# sensor_final_v1.net
KiCad netlist of a schematic drawn in EAGLE
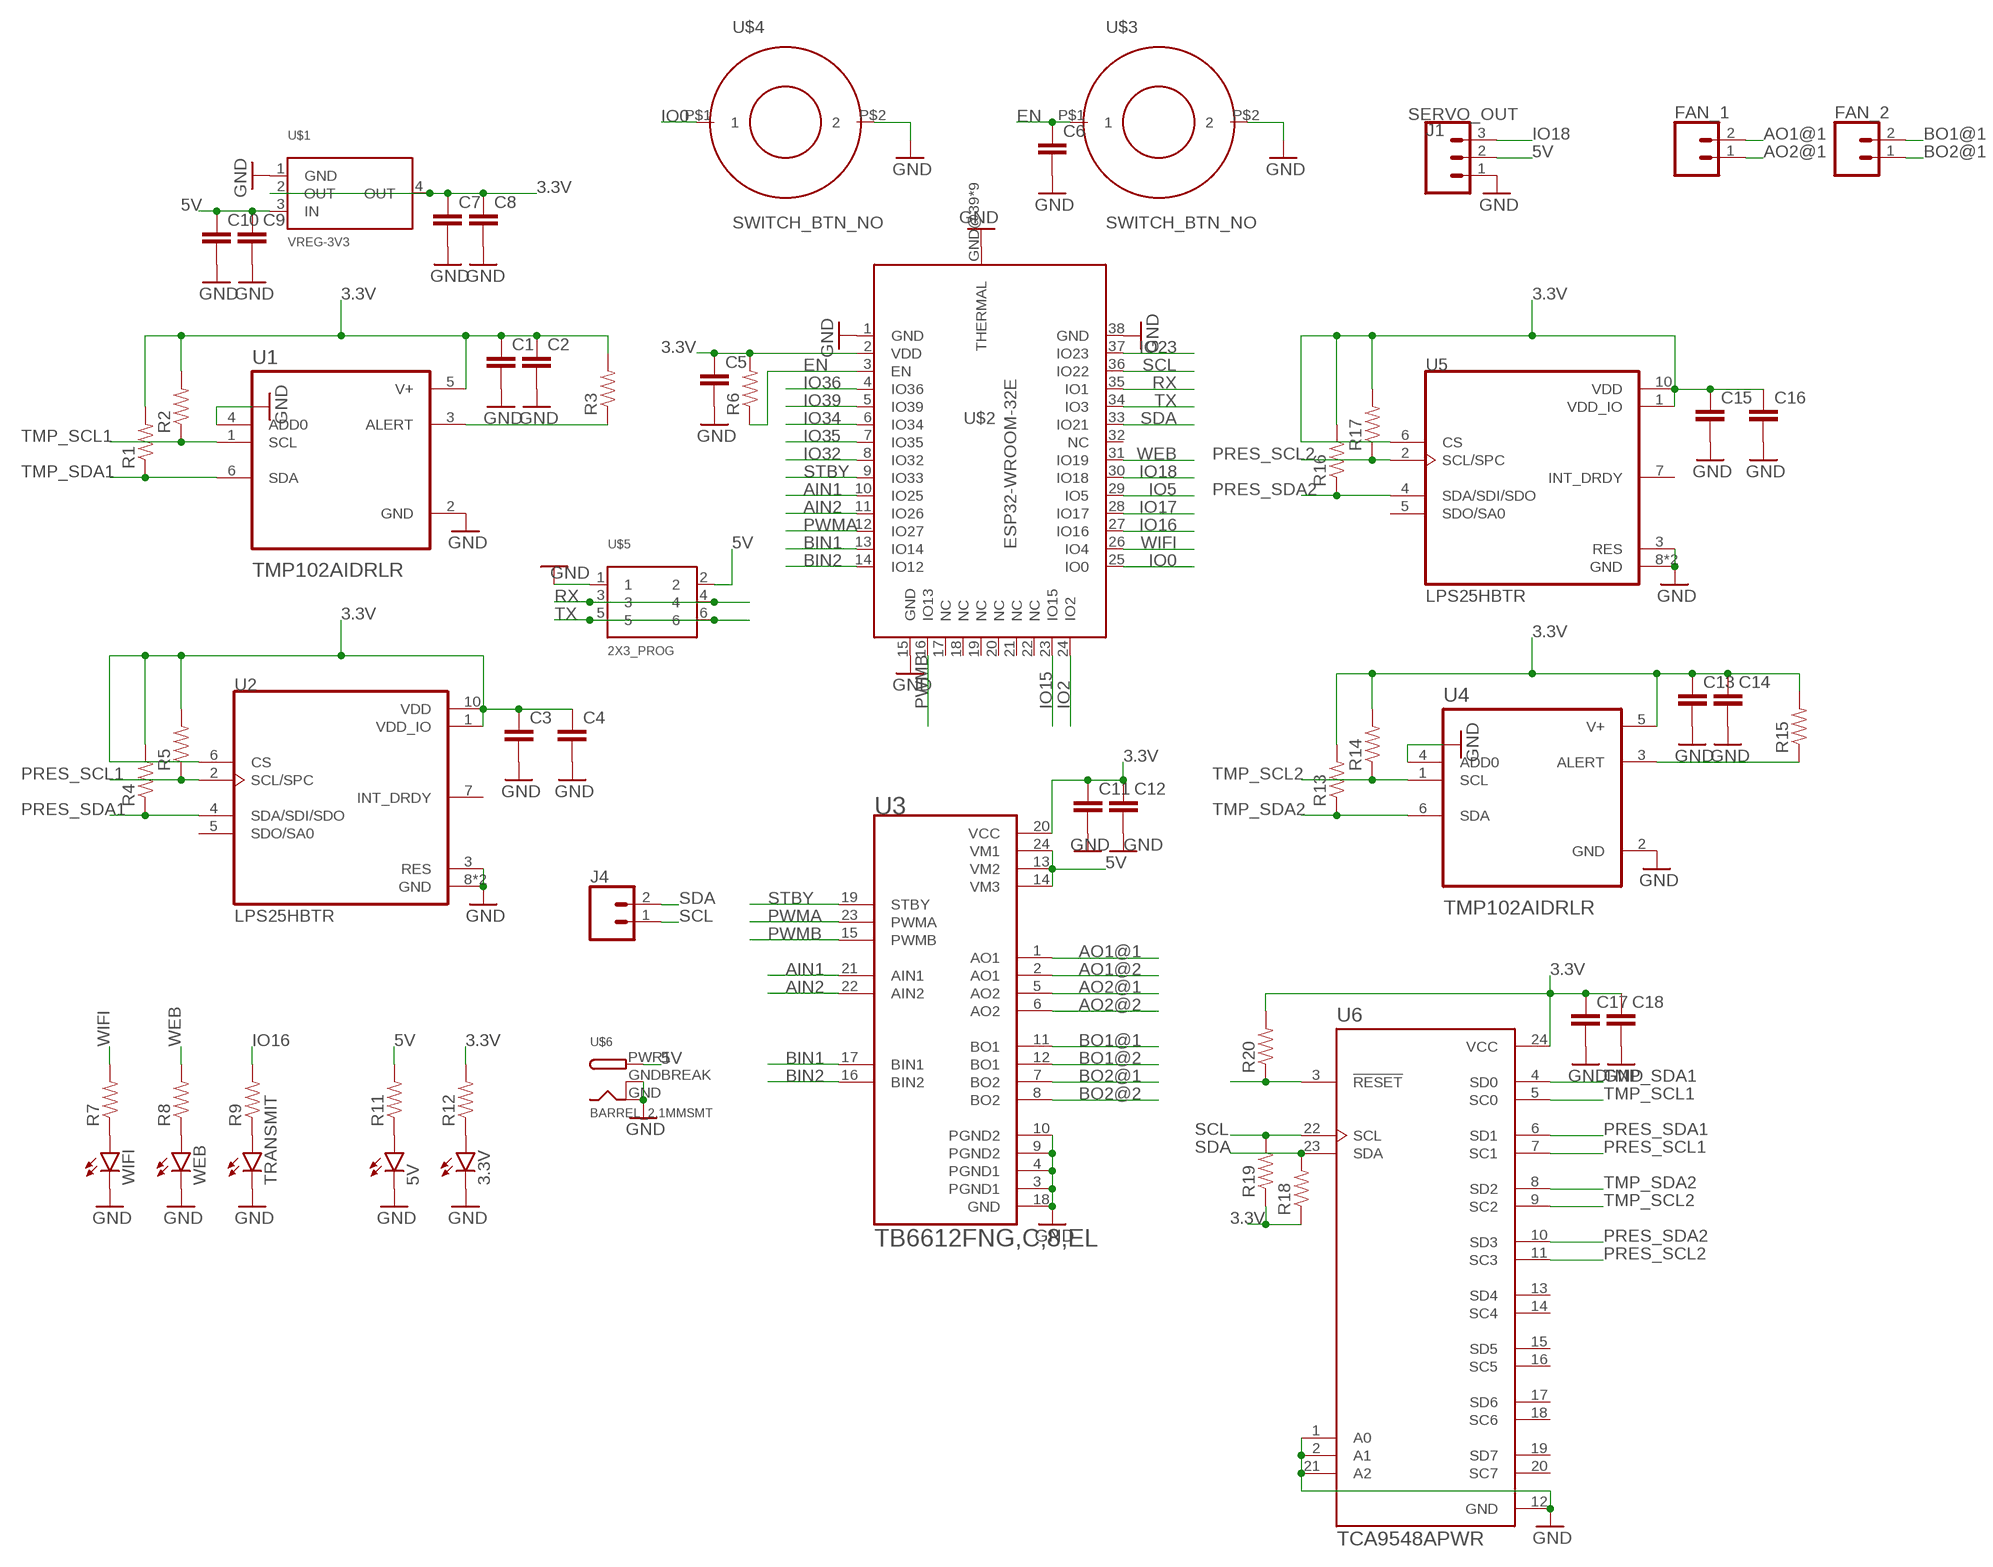
[diagram p0: schematic, sheet 1]

(export (version "E")
  (design (tool "Eeschema 10.0.6"))
  (components
    (comp (ref "3.3V")
      (value "LEDSMT1206")
      (footprint "eagle-import:1206")
      (libsource (lib "eagle-import") (part "LEDSMT1206"))
    )
    (comp (ref "5V")
      (value "LEDSMT1206")
      (footprint "eagle-import:1206")
      (libsource (lib "eagle-import") (part "LEDSMT1206"))
    )
    (comp (ref "C1")
      (value "CAP")
      (footprint "eagle-import:0805")
      (libsource (lib "eagle-import") (part "CAP"))
    )
    (comp (ref "C2")
      (value "CAP")
      (footprint "eagle-import:0805")
      (libsource (lib "eagle-import") (part "CAP"))
    )
    (comp (ref "C3")
      (value "CAP")
      (footprint "eagle-import:0805")
      (libsource (lib "eagle-import") (part "CAP"))
    )
    (comp (ref "C4")
      (value "CAP")
      (footprint "eagle-import:0805")
      (libsource (lib "eagle-import") (part "CAP"))
    )
    (comp (ref "C5")
      (value "CAP")
      (footprint "eagle-import:0805")
      (libsource (lib "eagle-import") (part "CAP"))
    )
    (comp (ref "C6")
      (value "CAP")
      (footprint "eagle-import:0805")
      (libsource (lib "eagle-import") (part "CAP"))
    )
    (comp (ref "C7")
      (value "CAP")
      (footprint "eagle-import:0805")
      (libsource (lib "eagle-import") (part "CAP"))
    )
    (comp (ref "C8")
      (value "CAP")
      (footprint "eagle-import:0805")
      (libsource (lib "eagle-import") (part "CAP"))
    )
    (comp (ref "C9")
      (value "CAP")
      (footprint "eagle-import:0805")
      (libsource (lib "eagle-import") (part "CAP"))
    )
    (comp (ref "C10")
      (value "CAP")
      (footprint "eagle-import:0805")
      (libsource (lib "eagle-import") (part "CAP"))
    )
    (comp (ref "C11")
      (value "CAP")
      (footprint "eagle-import:0805")
      (libsource (lib "eagle-import") (part "CAP"))
    )
    (comp (ref "C12")
      (value "CAP")
      (footprint "eagle-import:0805")
      (libsource (lib "eagle-import") (part "CAP"))
    )
    (comp (ref "C13")
      (value "CAP")
      (footprint "eagle-import:0805")
      (libsource (lib "eagle-import") (part "CAP"))
    )
    (comp (ref "C14")
      (value "CAP")
      (footprint "eagle-import:0805")
      (libsource (lib "eagle-import") (part "CAP"))
    )
    (comp (ref "C15")
      (value "CAP")
      (footprint "eagle-import:0805")
      (libsource (lib "eagle-import") (part "CAP"))
    )
    (comp (ref "C16")
      (value "CAP")
      (footprint "eagle-import:0805")
      (libsource (lib "eagle-import") (part "CAP"))
    )
    (comp (ref "C17")
      (value "CAP")
      (footprint "eagle-import:0805")
      (libsource (lib "eagle-import") (part "CAP"))
    )
    (comp (ref "C18")
      (value "CAP")
      (footprint "eagle-import:0805")
      (libsource (lib "eagle-import") (part "CAP"))
    )
    (comp (ref "FAN_1")
      (value "CONN_02")
      (footprint "eagle-import:1X02")
      (libsource (lib "eagle-import") (part "CONN_02"))
    )
    (comp (ref "FAN_2")
      (value "CONN_02")
      (footprint "eagle-import:1X02")
      (libsource (lib "eagle-import") (part "CONN_02"))
    )
    (comp (ref "J1")
      (value "SERVO_OUT")
      (footprint "eagle-import:1X03")
      (libsource (lib "eagle-import") (part "CONN_03"))
    )
    (comp (ref "J4")
      (value "CONN_02")
      (footprint "eagle-import:1X02")
      (libsource (lib "eagle-import") (part "CONN_02"))
    )
    (comp (ref "R1")
      (value "RES")
      (footprint "eagle-import:0805")
      (libsource (lib "eagle-import") (part "RES"))
    )
    (comp (ref "R2")
      (value "RES")
      (footprint "eagle-import:0805")
      (libsource (lib "eagle-import") (part "RES"))
    )
    (comp (ref "R3")
      (value "RES")
      (footprint "eagle-import:0805")
      (libsource (lib "eagle-import") (part "RES"))
    )
    (comp (ref "R4")
      (value "RES")
      (footprint "eagle-import:0805")
      (libsource (lib "eagle-import") (part "RES"))
    )
    (comp (ref "R5")
      (value "RES")
      (footprint "eagle-import:0805")
      (libsource (lib "eagle-import") (part "RES"))
    )
    (comp (ref "R6")
      (value "RES")
      (footprint "eagle-import:0805")
      (libsource (lib "eagle-import") (part "RES"))
    )
    (comp (ref "R7")
      (value "RES")
      (footprint "eagle-import:0805")
      (libsource (lib "eagle-import") (part "RES"))
    )
    (comp (ref "R8")
      (value "RES")
      (footprint "eagle-import:0805")
      (libsource (lib "eagle-import") (part "RES"))
    )
    (comp (ref "R9")
      (value "RES")
      (footprint "eagle-import:0805")
      (libsource (lib "eagle-import") (part "RES"))
    )
    (comp (ref "R11")
      (value "RES")
      (footprint "eagle-import:0805")
      (libsource (lib "eagle-import") (part "RES"))
    )
    (comp (ref "R12")
      (value "RES")
      (footprint "eagle-import:0805")
      (libsource (lib "eagle-import") (part "RES"))
    )
    (comp (ref "R13")
      (value "RES")
      (footprint "eagle-import:0805")
      (libsource (lib "eagle-import") (part "RES"))
    )
    (comp (ref "R14")
      (value "RES")
      (footprint "eagle-import:0805")
      (libsource (lib "eagle-import") (part "RES"))
    )
    (comp (ref "R15")
      (value "RES")
      (footprint "eagle-import:0805")
      (libsource (lib "eagle-import") (part "RES"))
    )
    (comp (ref "R16")
      (value "RES")
      (footprint "eagle-import:0805")
      (libsource (lib "eagle-import") (part "RES"))
    )
    (comp (ref "R17")
      (value "RES")
      (footprint "eagle-import:0805")
      (libsource (lib "eagle-import") (part "RES"))
    )
    (comp (ref "R18")
      (value "RES")
      (footprint "eagle-import:0805")
      (libsource (lib "eagle-import") (part "RES"))
    )
    (comp (ref "R19")
      (value "RES")
      (footprint "eagle-import:0805")
      (libsource (lib "eagle-import") (part "RES"))
    )
    (comp (ref "R20")
      (value "RES")
      (footprint "eagle-import:0805")
      (libsource (lib "eagle-import") (part "RES"))
    )
    (comp (ref "TRANSMIT")
      (value "LEDSMT1206")
      (footprint "eagle-import:1206")
      (libsource (lib "eagle-import") (part "LEDSMT1206"))
    )
    (comp (ref "U$1")
      (value "VREG-3V3")
      (footprint "eagle-import:R-PDSO-G4_TI")
      (libsource (lib "eagle-import") (part "VREG-3V3"))
    )
    (comp (ref "U$2")
      (value "ESP32-WROOM-32E")
      (footprint "eagle-import:ESP32-WROOM-32E")
      (libsource (lib "eagle-import") (part "ESP32-WROOM-32E"))
    )
    (comp (ref "U$3")
      (value "SWITCH_BTN_NO")
      (footprint "eagle-import:BTN_2")
      (libsource (lib "eagle-import") (part "SWITCH_BTN_NO"))
    )
    (comp (ref "U$4")
      (value "SWITCH_BTN_NO")
      (footprint "eagle-import:BTN_2")
      (libsource (lib "eagle-import") (part "SWITCH_BTN_NO"))
    )
    (comp (ref "U$5")
      (value "2X3_PROG")
      (footprint "eagle-import:2X3_0.1IN")
      (libsource (lib "eagle-import") (part "2X3_PROG"))
    )
    (comp (ref "U$6")
      (value "BARREL_2.1MMSMT")
      (footprint "eagle-import:DCJACK_2MM_SMT")
      (libsource (lib "eagle-import") (part "BARREL_2.1MMSMT"))
    )
    (comp (ref "U1")
      (value "TMP102AIDRLR")
      (footprint "eagle-import:SOT50P160X60-6N")
      (fields (field (name "MF") "Texas Instruments"))
      (libsource (lib "eagle-import") (part "TMP102AIDRLR"))
    )
    (comp (ref "U2")
      (value "LPS25HBTR")
      (footprint "eagle-import:PQFN60P250X250X80-10N")
      (fields (field (name "MF") "STMicroelectronics"))
      (libsource (lib "eagle-import") (part "LPS25HBTR"))
    )
    (comp (ref "U3")
      (value "TB6612FNG,C,8,EL")
      (footprint "eagle-import:SOP65P760X160-24N")
      (fields (field (name "MF") "Toshiba"))
      (libsource (lib "eagle-import") (part "TB6612FNG,C,8,EL"))
    )
    (comp (ref "U4")
      (value "TMP102AIDRLR")
      (footprint "eagle-import:SOT50P160X60-6N")
      (fields (field (name "MF") "Texas Instruments"))
      (libsource (lib "eagle-import") (part "TMP102AIDRLR"))
    )
    (comp (ref "U5")
      (value "LPS25HBTR")
      (footprint "eagle-import:PQFN60P250X250X80-10N")
      (fields (field (name "MF") "STMicroelectronics"))
      (libsource (lib "eagle-import") (part "LPS25HBTR"))
    )
    (comp (ref "U6")
      (value "TCA9548APWR")
      (footprint "eagle-import:SOP65P640X120-24N")
      (fields (field (name "MF") "Texas Instruments"))
      (libsource (lib "eagle-import") (part "TCA9548APWR"))
    )
    (comp (ref "WEB")
      (value "LEDSMT1206")
      (footprint "eagle-import:1206")
      (libsource (lib "eagle-import") (part "LEDSMT1206"))
    )
    (comp (ref "WIFI")
      (value "LEDSMT1206")
      (footprint "eagle-import:1206")
      (libsource (lib "eagle-import") (part "LEDSMT1206"))
    )
  )
  (nets
    (net (code "1") (name "/3.3V") (class "Default")
      (node (ref "C1") (pin "1") (pinfunction "1_1") (pintype "passive"))
      (node (ref "C11") (pin "1") (pinfunction "1_1") (pintype "passive"))
      (node (ref "C12") (pin "1") (pinfunction "1_1") (pintype "passive"))
      (node (ref "C13") (pin "1") (pinfunction "1_1") (pintype "passive"))
      (node (ref "C14") (pin "1") (pinfunction "1_1") (pintype "passive"))
      (node (ref "C15") (pin "1") (pinfunction "1_1") (pintype "passive"))
      (node (ref "C16") (pin "1") (pinfunction "1_1") (pintype "passive"))
      (node (ref "C17") (pin "1") (pinfunction "1_1") (pintype "passive"))
      (node (ref "C18") (pin "1") (pinfunction "1_1") (pintype "passive"))
      (node (ref "C2") (pin "1") (pinfunction "1_1") (pintype "passive"))
      (node (ref "C3") (pin "1") (pinfunction "1_1") (pintype "passive"))
      (node (ref "C4") (pin "1") (pinfunction "1_1") (pintype "passive"))
      (node (ref "C5") (pin "1") (pinfunction "1_1") (pintype "passive"))
      (node (ref "C7") (pin "1") (pinfunction "1_1") (pintype "passive"))
      (node (ref "C8") (pin "1") (pinfunction "1_1") (pintype "passive"))
      (node (ref "R1") (pin "2") (pinfunction "2_2") (pintype "passive"))
      (node (ref "R12") (pin "2") (pinfunction "2_2") (pintype "passive"))
      (node (ref "R13") (pin "2") (pinfunction "2_2") (pintype "passive"))
      (node (ref "R14") (pin "2") (pinfunction "2_2") (pintype "passive"))
      (node (ref "R15") (pin "2") (pinfunction "2_2") (pintype "passive"))
      (node (ref "R16") (pin "2") (pinfunction "2_2") (pintype "passive"))
      (node (ref "R17") (pin "2") (pinfunction "2_2") (pintype "passive"))
      (node (ref "R18") (pin "1") (pinfunction "1_1") (pintype "passive"))
      (node (ref "R19") (pin "1") (pinfunction "1_1") (pintype "passive"))
      (node (ref "R2") (pin "2") (pinfunction "2_2") (pintype "passive"))
      (node (ref "R20") (pin "2") (pinfunction "2_2") (pintype "passive"))
      (node (ref "R3") (pin "2") (pinfunction "2_2") (pintype "passive"))
      (node (ref "R4") (pin "2") (pinfunction "2_2") (pintype "passive"))
      (node (ref "R5") (pin "2") (pinfunction "2_2") (pintype "passive"))
      (node (ref "R6") (pin "2") (pinfunction "2_2") (pintype "passive"))
      (node (ref "U$1") (pin "2") (pinfunction "OUT_2") (pintype "bidirectional"))
      (node (ref "U$1") (pin "4") (pinfunction "OUT_4") (pintype "bidirectional"))
      (node (ref "U$2") (pin "2") (pinfunction "VDD_2") (pintype "bidirectional"))
      (node (ref "U1") (pin "5") (pinfunction "V+_5") (pintype "power_in"))
      (node (ref "U2") (pin "1") (pinfunction "VDD_IO_1") (pintype "power_in"))
      (node (ref "U2") (pin "10") (pinfunction "VDD_10") (pintype "power_in"))
      (node (ref "U2") (pin "6") (pinfunction "CS_6") (pintype "input"))
      (node (ref "U3") (pin "20") (pinfunction "VCC_20") (pintype "power_in"))
      (node (ref "U4") (pin "5") (pinfunction "V+_5") (pintype "power_in"))
      (node (ref "U5") (pin "1") (pinfunction "VDD_IO_1") (pintype "power_in"))
      (node (ref "U5") (pin "10") (pinfunction "VDD_10") (pintype "power_in"))
      (node (ref "U5") (pin "6") (pinfunction "CS_6") (pintype "input"))
      (node (ref "U6") (pin "24") (pinfunction "VCC_24") (pintype "power_in"))
    )
    (net (code "2") (name "/5V") (class "Default")
      (node (ref "C10") (pin "1") (pinfunction "1_1") (pintype "passive"))
      (node (ref "C9") (pin "1") (pinfunction "1_1") (pintype "passive"))
      (node (ref "J1") (pin "2") (pinfunction "2_2") (pintype "passive"))
      (node (ref "R11") (pin "2") (pinfunction "2_2") (pintype "passive"))
      (node (ref "U$1") (pin "3") (pinfunction "IN_3") (pintype "bidirectional"))
      (node (ref "U$5") (pin "2") (pinfunction "2_2") (pintype "bidirectional"))
      (node (ref "U$6") (pin "PWR1") (pinfunction "PWR_PWR1") (pintype "power_in"))
      (node (ref "U3") (pin "13") (pinfunction "VM2_13") (pintype "power_in"))
      (node (ref "U3") (pin "14") (pinfunction "VM3_14") (pintype "power_in"))
      (node (ref "U3") (pin "24") (pinfunction "VM1_24") (pintype "power_in"))
    )
    (net (code "3") (name "/AIN1") (class "Default")
      (node (ref "U$2") (pin "10") (pinfunction "IO25_10") (pintype "bidirectional"))
      (node (ref "U3") (pin "21") (pinfunction "AIN1_21") (pintype "input"))
    )
    (net (code "4") (name "/AIN2") (class "Default")
      (node (ref "U$2") (pin "11") (pinfunction "IO26_11") (pintype "bidirectional"))
      (node (ref "U3") (pin "22") (pinfunction "AIN2_22") (pintype "input"))
    )
    (net (code "5") (name "/AO1@1") (class "Default")
      (node (ref "FAN_1") (pin "2") (pinfunction "2_2") (pintype "passive"))
      (node (ref "U3") (pin "1") (pinfunction "AO1_1") (pintype "output"))
    )
    (net (code "6") (name "/AO1@2") (class "Default")
      (node (ref "U3") (pin "2") (pinfunction "AO1_2") (pintype "output"))
    )
    (net (code "7") (name "/AO2@1") (class "Default")
      (node (ref "FAN_1") (pin "1") (pinfunction "1_1") (pintype "passive"))
      (node (ref "U3") (pin "5") (pinfunction "AO2_5") (pintype "output"))
    )
    (net (code "8") (name "/AO2@2") (class "Default")
      (node (ref "U3") (pin "6") (pinfunction "AO2_6") (pintype "output"))
    )
    (net (code "9") (name "/BIN1") (class "Default")
      (node (ref "U$2") (pin "13") (pinfunction "IO14_13") (pintype "bidirectional"))
      (node (ref "U3") (pin "17") (pinfunction "BIN1_17") (pintype "input"))
    )
    (net (code "10") (name "/BIN2") (class "Default")
      (node (ref "U$2") (pin "14") (pinfunction "IO12_14") (pintype "bidirectional"))
      (node (ref "U3") (pin "16") (pinfunction "BIN2_16") (pintype "input"))
    )
    (net (code "11") (name "/BO1@1") (class "Default")
      (node (ref "FAN_2") (pin "2") (pinfunction "2_2") (pintype "passive"))
      (node (ref "U3") (pin "11") (pinfunction "BO1_11") (pintype "output"))
    )
    (net (code "12") (name "/BO1@2") (class "Default")
      (node (ref "U3") (pin "12") (pinfunction "BO1_12") (pintype "output"))
    )
    (net (code "13") (name "/BO2@1") (class "Default")
      (node (ref "FAN_2") (pin "1") (pinfunction "1_1") (pintype "passive"))
      (node (ref "U3") (pin "7") (pinfunction "BO2_7") (pintype "output"))
    )
    (net (code "14") (name "/BO2@2") (class "Default")
      (node (ref "U3") (pin "8") (pinfunction "BO2_8") (pintype "output"))
    )
    (net (code "15") (name "/EN") (class "Default")
      (node (ref "C6") (pin "1") (pinfunction "1_1") (pintype "passive"))
      (node (ref "R6") (pin "1") (pinfunction "1_1") (pintype "passive"))
      (node (ref "U$2") (pin "3") (pinfunction "EN_3") (pintype "bidirectional"))
      (node (ref "U$3") (pin "P$1") (pinfunction "1_P$1") (pintype "bidirectional"))
    )
    (net (code "16") (name "/IO0") (class "Default")
      (node (ref "U$2") (pin "25") (pinfunction "IO0_25") (pintype "bidirectional"))
      (node (ref "U$4") (pin "P$1") (pinfunction "1_P$1") (pintype "bidirectional"))
    )
    (net (code "17") (name "/IO2") (class "Default")
      (node (ref "U$2") (pin "24") (pinfunction "IO2_24") (pintype "bidirectional"))
    )
    (net (code "18") (name "/IO5") (class "Default")
      (node (ref "U$2") (pin "29") (pinfunction "IO5_29") (pintype "bidirectional"))
    )
    (net (code "19") (name "/IO15") (class "Default")
      (node (ref "U$2") (pin "23") (pinfunction "IO15_23") (pintype "bidirectional"))
    )
    (net (code "20") (name "/IO16") (class "Default")
      (node (ref "R9") (pin "2") (pinfunction "2_2") (pintype "passive"))
      (node (ref "U$2") (pin "27") (pinfunction "IO16_27") (pintype "bidirectional"))
    )
    (net (code "21") (name "/IO17") (class "Default")
      (node (ref "U$2") (pin "28") (pinfunction "IO17_28") (pintype "bidirectional"))
    )
    (net (code "22") (name "/IO18") (class "Default")
      (node (ref "J1") (pin "3") (pinfunction "3_3") (pintype "passive"))
      (node (ref "U$2") (pin "30") (pinfunction "IO18_30") (pintype "bidirectional"))
    )
    (net (code "23") (name "/IO23") (class "Default")
      (node (ref "U$2") (pin "37") (pinfunction "IO23_37") (pintype "bidirectional"))
    )
    (net (code "24") (name "/IO32") (class "Default")
      (node (ref "U$2") (pin "8") (pinfunction "IO32_8") (pintype "bidirectional"))
    )
    (net (code "25") (name "/IO34") (class "Default")
      (node (ref "U$2") (pin "6") (pinfunction "IO34_6") (pintype "bidirectional"))
    )
    (net (code "26") (name "/IO35") (class "Default")
      (node (ref "U$2") (pin "7") (pinfunction "IO35_7") (pintype "bidirectional"))
    )
    (net (code "27") (name "/IO36") (class "Default")
      (node (ref "U$2") (pin "4") (pinfunction "IO36_4") (pintype "bidirectional"))
    )
    (net (code "28") (name "/IO39") (class "Default")
      (node (ref "U$2") (pin "5") (pinfunction "IO39_5") (pintype "bidirectional"))
    )
    (net (code "29") (name "/PRES_SCL1") (class "Default")
      (node (ref "R5") (pin "1") (pinfunction "1_1") (pintype "passive"))
      (node (ref "U2") (pin "2") (pinfunction "SCL/SPC_2") (pintype "input"))
      (node (ref "U6") (pin "7") (pinfunction "SC1_7") (pintype "bidirectional"))
    )
    (net (code "30") (name "/PRES_SCL2") (class "Default")
      (node (ref "R17") (pin "1") (pinfunction "1_1") (pintype "passive"))
      (node (ref "U5") (pin "2") (pinfunction "SCL/SPC_2") (pintype "input"))
      (node (ref "U6") (pin "11") (pinfunction "SC3_11") (pintype "bidirectional"))
    )
    (net (code "31") (name "/PRES_SDA1") (class "Default")
      (node (ref "R4") (pin "1") (pinfunction "1_1") (pintype "passive"))
      (node (ref "U2") (pin "4") (pinfunction "SDA/SDI/SDO_4") (pintype "bidirectional"))
      (node (ref "U6") (pin "6") (pinfunction "SD1_6") (pintype "bidirectional"))
    )
    (net (code "32") (name "/PRES_SDA2") (class "Default")
      (node (ref "R16") (pin "1") (pinfunction "1_1") (pintype "passive"))
      (node (ref "U5") (pin "4") (pinfunction "SDA/SDI/SDO_4") (pintype "bidirectional"))
      (node (ref "U6") (pin "10") (pinfunction "SD3_10") (pintype "bidirectional"))
    )
    (net (code "33") (name "/PWMA") (class "Default")
      (node (ref "U$2") (pin "12") (pinfunction "IO27_12") (pintype "bidirectional"))
      (node (ref "U3") (pin "23") (pinfunction "PWMA_23") (pintype "input"))
    )
    (net (code "34") (name "/PWMB") (class "Default")
      (node (ref "U$2") (pin "16") (pinfunction "IO13_16") (pintype "bidirectional"))
      (node (ref "U3") (pin "15") (pinfunction "PWMB_15") (pintype "input"))
    )
    (net (code "35") (name "/RX") (class "Default")
      (node (ref "U$2") (pin "35") (pinfunction "IO1_35") (pintype "bidirectional"))
      (node (ref "U$5") (pin "3") (pinfunction "3_3") (pintype "bidirectional"))
      (node (ref "U$5") (pin "4") (pinfunction "4_4") (pintype "bidirectional"))
    )
    (net (code "36") (name "/SCL") (class "Default")
      (node (ref "J4") (pin "1") (pinfunction "1_1") (pintype "passive"))
      (node (ref "R19") (pin "2") (pinfunction "2_2") (pintype "passive"))
      (node (ref "U$2") (pin "36") (pinfunction "IO22_36") (pintype "bidirectional"))
      (node (ref "U6") (pin "22") (pinfunction "SCL_22") (pintype "input"))
    )
    (net (code "37") (name "/SDA") (class "Default")
      (node (ref "J4") (pin "2") (pinfunction "2_2") (pintype "passive"))
      (node (ref "R18") (pin "2") (pinfunction "2_2") (pintype "passive"))
      (node (ref "U$2") (pin "33") (pinfunction "IO21_33") (pintype "bidirectional"))
      (node (ref "U6") (pin "23") (pinfunction "SDA_23") (pintype "bidirectional"))
    )
    (net (code "38") (name "/STBY") (class "Default")
      (node (ref "U$2") (pin "9") (pinfunction "IO33_9") (pintype "bidirectional"))
      (node (ref "U3") (pin "19") (pinfunction "STBY_19") (pintype "input"))
    )
    (net (code "39") (name "/TMP_SCL1") (class "Default")
      (node (ref "R2") (pin "1") (pinfunction "1_1") (pintype "passive"))
      (node (ref "U1") (pin "1") (pinfunction "SCL_1") (pintype "input"))
      (node (ref "U6") (pin "5") (pinfunction "SC0_5") (pintype "bidirectional"))
    )
    (net (code "40") (name "/TMP_SCL2") (class "Default")
      (node (ref "R14") (pin "1") (pinfunction "1_1") (pintype "passive"))
      (node (ref "U4") (pin "1") (pinfunction "SCL_1") (pintype "input"))
      (node (ref "U6") (pin "9") (pinfunction "SC2_9") (pintype "bidirectional"))
    )
    (net (code "41") (name "/TMP_SDA1") (class "Default")
      (node (ref "R1") (pin "1") (pinfunction "1_1") (pintype "passive"))
      (node (ref "U1") (pin "6") (pinfunction "SDA_6") (pintype "bidirectional"))
      (node (ref "U6") (pin "4") (pinfunction "SD0_4") (pintype "bidirectional"))
    )
    (net (code "42") (name "/TMP_SDA2") (class "Default")
      (node (ref "R13") (pin "1") (pinfunction "1_1") (pintype "passive"))
      (node (ref "U4") (pin "6") (pinfunction "SDA_6") (pintype "bidirectional"))
      (node (ref "U6") (pin "8") (pinfunction "SD2_8") (pintype "bidirectional"))
    )
    (net (code "43") (name "/TX") (class "Default")
      (node (ref "U$2") (pin "34") (pinfunction "IO3_34") (pintype "bidirectional"))
      (node (ref "U$5") (pin "5") (pinfunction "5_5") (pintype "bidirectional"))
      (node (ref "U$5") (pin "6") (pinfunction "6_6") (pintype "bidirectional"))
    )
    (net (code "44") (name "/WEB") (class "Default")
      (node (ref "R8") (pin "2") (pinfunction "2_2") (pintype "passive"))
      (node (ref "U$2") (pin "31") (pinfunction "IO19_31") (pintype "bidirectional"))
    )
    (net (code "45") (name "/WIFI") (class "Default")
      (node (ref "R7") (pin "2") (pinfunction "2_2") (pintype "passive"))
      (node (ref "U$2") (pin "26") (pinfunction "IO4_26") (pintype "bidirectional"))
    )
    (net (code "46") (name "GND") (class "Default")
      (node (ref "3.3V") (pin "C") (pinfunction "C_C") (pintype "passive"))
      (node (ref "5V") (pin "C") (pinfunction "C_C") (pintype "passive"))
      (node (ref "C1") (pin "2") (pinfunction "2_2") (pintype "passive"))
      (node (ref "C10") (pin "2") (pinfunction "2_2") (pintype "passive"))
      (node (ref "C11") (pin "2") (pinfunction "2_2") (pintype "passive"))
      (node (ref "C12") (pin "2") (pinfunction "2_2") (pintype "passive"))
      (node (ref "C13") (pin "2") (pinfunction "2_2") (pintype "passive"))
      (node (ref "C14") (pin "2") (pinfunction "2_2") (pintype "passive"))
      (node (ref "C15") (pin "2") (pinfunction "2_2") (pintype "passive"))
      (node (ref "C16") (pin "2") (pinfunction "2_2") (pintype "passive"))
      (node (ref "C17") (pin "2") (pinfunction "2_2") (pintype "passive"))
      (node (ref "C18") (pin "2") (pinfunction "2_2") (pintype "passive"))
      (node (ref "C2") (pin "2") (pinfunction "2_2") (pintype "passive"))
      (node (ref "C3") (pin "2") (pinfunction "2_2") (pintype "passive"))
      (node (ref "C4") (pin "2") (pinfunction "2_2") (pintype "passive"))
      (node (ref "C5") (pin "2") (pinfunction "2_2") (pintype "passive"))
      (node (ref "C6") (pin "2") (pinfunction "2_2") (pintype "passive"))
      (node (ref "C7") (pin "2") (pinfunction "2_2") (pintype "passive"))
      (node (ref "C8") (pin "2") (pinfunction "2_2") (pintype "passive"))
      (node (ref "C9") (pin "2") (pinfunction "2_2") (pintype "passive"))
      (node (ref "J1") (pin "1") (pinfunction "1_1") (pintype "passive"))
      (node (ref "TRANSMIT") (pin "C") (pinfunction "C_C") (pintype "passive"))
      (node (ref "U$1") (pin "1") (pinfunction "GND_1") (pintype "bidirectional"))
      (node (ref "U$2") (pin "1") (pinfunction "GND_1") (pintype "bidirectional"))
      (node (ref "U$2") (pin "15") (pinfunction "GND_15") (pintype "bidirectional"))
      (node (ref "U$2") (pin "38") (pinfunction "GND_38") (pintype "bidirectional"))
      (node (ref "U$2") (pin "GND@39") (pinfunction "THERMAL_GND@39") (pintype "bidirectional"))
      (node (ref "U$2") (pin "GND@40") (pinfunction "THERMAL_GND@40") (pintype "bidirectional"))
      (node (ref "U$2") (pin "GND@41") (pinfunction "THERMAL_GND@41") (pintype "bidirectional"))
      (node (ref "U$2") (pin "GND@42") (pinfunction "THERMAL_GND@42") (pintype "bidirectional"))
      (node (ref "U$2") (pin "GND@43") (pinfunction "THERMAL_GND@43") (pintype "bidirectional"))
      (node (ref "U$2") (pin "GND@44") (pinfunction "THERMAL_GND@44") (pintype "bidirectional"))
      (node (ref "U$2") (pin "GND@45") (pinfunction "THERMAL_GND@45") (pintype "bidirectional"))
      (node (ref "U$2") (pin "GND@46") (pinfunction "THERMAL_GND@46") (pintype "bidirectional"))
      (node (ref "U$2") (pin "GND@47") (pinfunction "THERMAL_GND@47") (pintype "bidirectional"))
      (node (ref "U$3") (pin "P$2") (pinfunction "2_P$2") (pintype "bidirectional"))
      (node (ref "U$4") (pin "P$2") (pinfunction "2_P$2") (pintype "bidirectional"))
      (node (ref "U$5") (pin "1") (pinfunction "1_1") (pintype "bidirectional"))
      (node (ref "U$6") (pin "GND") (pinfunction "GND_GND") (pintype "power_in"))
      (node (ref "U$6") (pin "GNDBREAK") (pinfunction "GNDBREAK_GNDBREAK") (pintype "power_in"))
      (node (ref "U1") (pin "2") (pinfunction "GND_2") (pintype "power_in"))
      (node (ref "U1") (pin "4") (pinfunction "ADD0_4") (pintype "input"))
      (node (ref "U2") (pin "3") (pinfunction "RES_3") (pintype "power_in"))
      (node (ref "U2") (pin "8") (pinfunction "GND_8") (pintype "power_in"))
      (node (ref "U2") (pin "9") (pinfunction "GND_9") (pintype "power_in"))
      (node (ref "U3") (pin "10") (pinfunction "PGND2_10") (pintype "passive"))
      (node (ref "U3") (pin "18") (pinfunction "GND_18") (pintype "passive"))
      (node (ref "U3") (pin "3") (pinfunction "PGND1_3") (pintype "passive"))
      (node (ref "U3") (pin "4") (pinfunction "PGND1_4") (pintype "passive"))
      (node (ref "U3") (pin "9") (pinfunction "PGND2_9") (pintype "passive"))
      (node (ref "U4") (pin "2") (pinfunction "GND_2") (pintype "power_in"))
      (node (ref "U4") (pin "4") (pinfunction "ADD0_4") (pintype "input"))
      (node (ref "U5") (pin "3") (pinfunction "RES_3") (pintype "power_in"))
      (node (ref "U5") (pin "8") (pinfunction "GND_8") (pintype "power_in"))
      (node (ref "U5") (pin "9") (pinfunction "GND_9") (pintype "power_in"))
      (node (ref "U6") (pin "1") (pinfunction "A0_1") (pintype "input"))
      (node (ref "U6") (pin "12") (pinfunction "GND_12") (pintype "power_in"))
      (node (ref "U6") (pin "2") (pinfunction "A1_2") (pintype "input"))
      (node (ref "U6") (pin "21") (pinfunction "A2_21") (pintype "input"))
      (node (ref "WEB") (pin "C") (pinfunction "C_C") (pintype "passive"))
      (node (ref "WIFI") (pin "C") (pinfunction "C_C") (pintype "passive"))
    )
    (net (code "47") (name "Net-(3.3V-PadA)") (class "Default")
      (node (ref "3.3V") (pin "A") (pinfunction "A_A") (pintype "passive"))
      (node (ref "R12") (pin "1") (pinfunction "1_1") (pintype "passive"))
    )
    (net (code "48") (name "Net-(5V-PadA)") (class "Default")
      (node (ref "5V") (pin "A") (pinfunction "A_A") (pintype "passive"))
      (node (ref "R11") (pin "1") (pinfunction "1_1") (pintype "passive"))
    )
    (net (code "49") (name "Net-(R7-Pad1)") (class "Default")
      (node (ref "R7") (pin "1") (pinfunction "1_1") (pintype "passive"))
      (node (ref "WIFI") (pin "A") (pinfunction "A_A") (pintype "passive"))
    )
    (net (code "50") (name "Net-(R8-Pad1)") (class "Default")
      (node (ref "R8") (pin "1") (pinfunction "1_1") (pintype "passive"))
      (node (ref "WEB") (pin "A") (pinfunction "A_A") (pintype "passive"))
    )
    (net (code "51") (name "Net-(R9-Pad1)") (class "Default")
      (node (ref "R9") (pin "1") (pinfunction "1_1") (pintype "passive"))
      (node (ref "TRANSMIT") (pin "A") (pinfunction "A_A") (pintype "passive"))
    )
    (net (code "52") (name "Net-(U1-ALERT)") (class "Default")
      (node (ref "R3") (pin "1") (pinfunction "1_1") (pintype "passive"))
      (node (ref "U1") (pin "3") (pinfunction "ALERT_3") (pintype "output"))
    )
    (net (code "53") (name "Net-(U4-ALERT)") (class "Default")
      (node (ref "R15") (pin "1") (pinfunction "1_1") (pintype "passive"))
      (node (ref "U4") (pin "3") (pinfunction "ALERT_3") (pintype "output"))
    )
    (net (code "54") (name "Net-(U6-~{RESET})") (class "Default")
      (node (ref "R20") (pin "1") (pinfunction "1_1") (pintype "passive"))
      (node (ref "U6") (pin "3") (pinfunction "~{RESET}_3") (pintype "input"))
    )
    (net (code "55") (name "unconnected-(U$2-NC-Pad17)") (class "Default")
      (node (ref "U$2") (pin "17") (pinfunction "NC_17") (pintype "bidirectional"))
    )
    (net (code "56") (name "unconnected-(U$2-NC-Pad18)") (class "Default")
      (node (ref "U$2") (pin "18") (pinfunction "NC_18") (pintype "bidirectional"))
    )
    (net (code "57") (name "unconnected-(U$2-NC-Pad19)") (class "Default")
      (node (ref "U$2") (pin "19") (pinfunction "NC_19") (pintype "bidirectional"))
    )
    (net (code "58") (name "unconnected-(U$2-NC-Pad20)") (class "Default")
      (node (ref "U$2") (pin "20") (pinfunction "NC_20") (pintype "bidirectional"))
    )
    (net (code "59") (name "unconnected-(U$2-NC-Pad21)") (class "Default")
      (node (ref "U$2") (pin "21") (pinfunction "NC_21") (pintype "bidirectional"))
    )
    (net (code "60") (name "unconnected-(U$2-NC-Pad22)") (class "Default")
      (node (ref "U$2") (pin "22") (pinfunction "NC_22") (pintype "bidirectional"))
    )
    (net (code "61") (name "unconnected-(U$2-NC-Pad32)") (class "Default")
      (node (ref "U$2") (pin "32") (pinfunction "NC_32") (pintype "bidirectional"))
    )
    (net (code "62") (name "unconnected-(U2-INT_DRDY-Pad7)") (class "Default")
      (node (ref "U2") (pin "7") (pinfunction "INT_DRDY_7") (pintype "output"))
    )
    (net (code "63") (name "unconnected-(U2-SDO{slash}SA0-Pad5)") (class "Default")
      (node (ref "U2") (pin "5") (pinfunction "SDO/SA0_5") (pintype "bidirectional"))
    )
    (net (code "64") (name "unconnected-(U5-INT_DRDY-Pad7)") (class "Default")
      (node (ref "U5") (pin "7") (pinfunction "INT_DRDY_7") (pintype "output"))
    )
    (net (code "65") (name "unconnected-(U5-SDO{slash}SA0-Pad5)") (class "Default")
      (node (ref "U5") (pin "5") (pinfunction "SDO/SA0_5") (pintype "bidirectional"))
    )
    (net (code "66") (name "unconnected-(U6-SC4-Pad14)") (class "Default")
      (node (ref "U6") (pin "14") (pinfunction "SC4_14") (pintype "bidirectional"))
    )
    (net (code "67") (name "unconnected-(U6-SC5-Pad16)") (class "Default")
      (node (ref "U6") (pin "16") (pinfunction "SC5_16") (pintype "bidirectional"))
    )
    (net (code "68") (name "unconnected-(U6-SC6-Pad18)") (class "Default")
      (node (ref "U6") (pin "18") (pinfunction "SC6_18") (pintype "bidirectional"))
    )
    (net (code "69") (name "unconnected-(U6-SC7-Pad20)") (class "Default")
      (node (ref "U6") (pin "20") (pinfunction "SC7_20") (pintype "bidirectional"))
    )
    (net (code "70") (name "unconnected-(U6-SD4-Pad13)") (class "Default")
      (node (ref "U6") (pin "13") (pinfunction "SD4_13") (pintype "bidirectional"))
    )
    (net (code "71") (name "unconnected-(U6-SD5-Pad15)") (class "Default")
      (node (ref "U6") (pin "15") (pinfunction "SD5_15") (pintype "bidirectional"))
    )
    (net (code "72") (name "unconnected-(U6-SD6-Pad17)") (class "Default")
      (node (ref "U6") (pin "17") (pinfunction "SD6_17") (pintype "bidirectional"))
    )
    (net (code "73") (name "unconnected-(U6-SD7-Pad19)") (class "Default")
      (node (ref "U6") (pin "19") (pinfunction "SD7_19") (pintype "bidirectional"))
    )
  )
)
